# Relay.net
KiCad netlist of a schematic drawn in Altium Designer
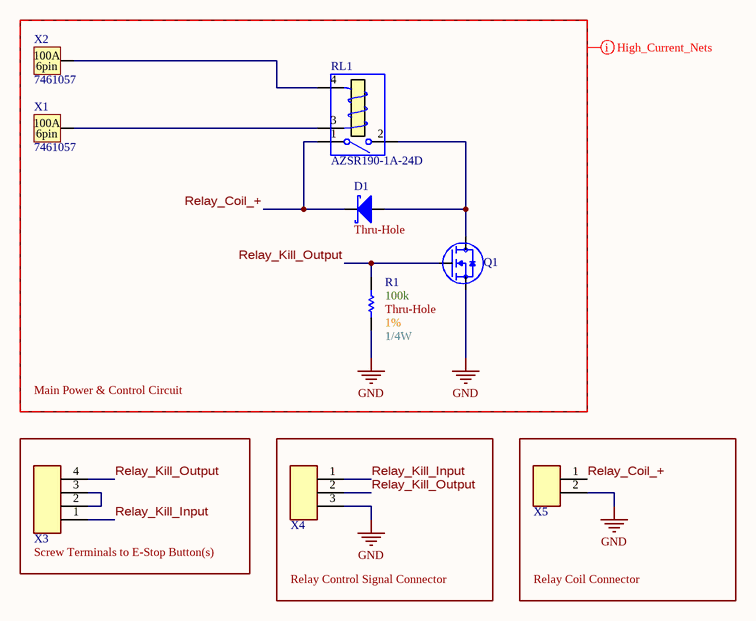
[diagram p0: Relay.SchDoc]

(export (version "E")
  (design (tool "Eeschema 10.0.6"))
  (components
    (comp (ref "D1")
      (value "1N5822")
      (footprint "Thru-Hole")
      (libsource (lib "Diodes") (part "[Schottky] Thru-Hole 40V 3A"))
    )
    (comp (ref "Q1")
      (value "[NMOS] SMD 20V 1.4A 160mOhm")
      (footprint "SOT323")
      (description "BSS816NWH6327XTSA1")
      (libsource (lib "Transistors") (part "[NMOS] SMD 20V 1.4A 160mOhm"))
    )
    (comp (ref "R1")
      (value "[100k] Thru-Hole 1% 1/4W")
      (footprint "[Res] Thru-Hole 1/4W")
      (description "MFR-25FTF52-100K")
      (fields
        (field (name "SIZE PACKAGE") "Thru-Hole")
        (field (name "WATTAGE") "1/4W")
        (field (name "TOLERANCE") "1%")
        (field (name "RESISTANCE") "100k")
      )
      (libsource (lib "Resistors") (part "[100k] Thru-Hole 1% 1/4W"))
    )
    (comp (ref "RL1")
      (value "AZSR190-1A-24D")
      (footprint "[Relay] AZSR190-1A-24D")
      (libsource (lib "RADM Components") (part "[Relay] AZSR190-1A-24D"))
    )
    (comp (ref "X1")
      (value "7461057")
      (footprint "[Port] Shank Connector (100A)")
      (description "7461057, internal thread")
      (libsource (lib "RADM Connectors") (part "[Port] Shank Connector (100A)"))
    )
    (comp (ref "X2")
      (value "7461057")
      (footprint "[Port] Shank Connector (100A)")
      (description "7461057, internal thread")
      (libsource (lib "RADM Connectors") (part "[Port] Shank Connector (100A)"))
    )
    (comp (ref "X3")
      (value "4pin Screw Terminal")
      (footprint "[Screw Terminal] 4pin 5mm")
      (description "TB002-500-04BE")
      (libsource (lib "Connectors") (part "[Screw Terminal] 4pin"))
    )
    (comp (ref "X4")
      (value "[Sherlock] 3pin")
      (footprint "[Sherlock] 3pin")
      (description "0353620350")
      (libsource (lib "Connectors") (part "[Sherlock] 3pin"))
    )
    (comp (ref "X5")
      (value "2pin Screw Terminal")
      (footprint "[Screw Terminal] 2pin 5mm")
      (description "TB002-500-02BE")
      (libsource (lib "Connectors") (part "[Screw Terminal] 2pin"))
    )
  )
  (nets
    (net (code "1") (name "/Relay_Coil_+") (class "Default")
      (node (ref "D1") (pin "1") (pinfunction "K_1") (pintype "passive"))
      (node (ref "RL1") (pin "1") (pinfunction "1_1") (pintype "passive"))
      (node (ref "X5") (pin "1") (pintype "power_in"))
    )
    (net (code "2") (name "/Relay_Kill_Input") (class "Default")
      (node (ref "X3") (pin "1") (pintype "power_in"))
      (node (ref "X4") (pin "1") (pintype "passive"))
    )
    (net (code "3") (name "/Relay_Kill_Output") (class "Default")
      (node (ref "Q1") (pin "1") (pinfunction "Gate_1") (pintype "passive"))
      (node (ref "R1") (pin "2") (pinfunction "2_2") (pintype "passive"))
      (node (ref "X3") (pin "4") (pintype "power_in"))
      (node (ref "X4") (pin "2") (pintype "passive"))
    )
    (net (code "4") (name "GND") (class "Default")
      (node (ref "Q1") (pin "2") (pinfunction "Source_2") (pintype "passive"))
      (node (ref "R1") (pin "1") (pinfunction "1_1") (pintype "passive"))
      (node (ref "X4") (pin "3") (pintype "passive"))
      (node (ref "X5") (pin "2") (pintype "power_in"))
    )
    (net (code "5") (name "Net-(D1-A)") (class "Default")
      (node (ref "D1") (pin "2") (pinfunction "A_2") (pintype "passive"))
      (node (ref "Q1") (pin "3") (pinfunction "Drain_3") (pintype "passive"))
      (node (ref "RL1") (pin "2") (pinfunction "2_2") (pintype "passive"))
    )
    (net (code "6") (name "Net-(RL1-T1)") (class "Default")
      (node (ref "RL1") (pin "3") (pinfunction "T1_3") (pintype "passive"))
      (node (ref "X1") (pin "1") (pinfunction "4_1") (pintype "power_in"))
    )
    (net (code "7") (name "Net-(RL1-T2)") (class "Default")
      (node (ref "RL1") (pin "4") (pinfunction "T2_4") (pintype "passive"))
      (node (ref "X2") (pin "1") (pinfunction "4_1") (pintype "power_in"))
    )
    (net (code "8") (name "Net-(X3-Pad2)") (class "Default")
      (node (ref "X3") (pin "2") (pintype "power_in"))
      (node (ref "X3") (pin "3") (pintype "power_in"))
    )
  )
)
